# SCH_DART-Flight-Computer-4_2024-07-14.net
KiCad netlist of a schematic drawn in EasyEDA
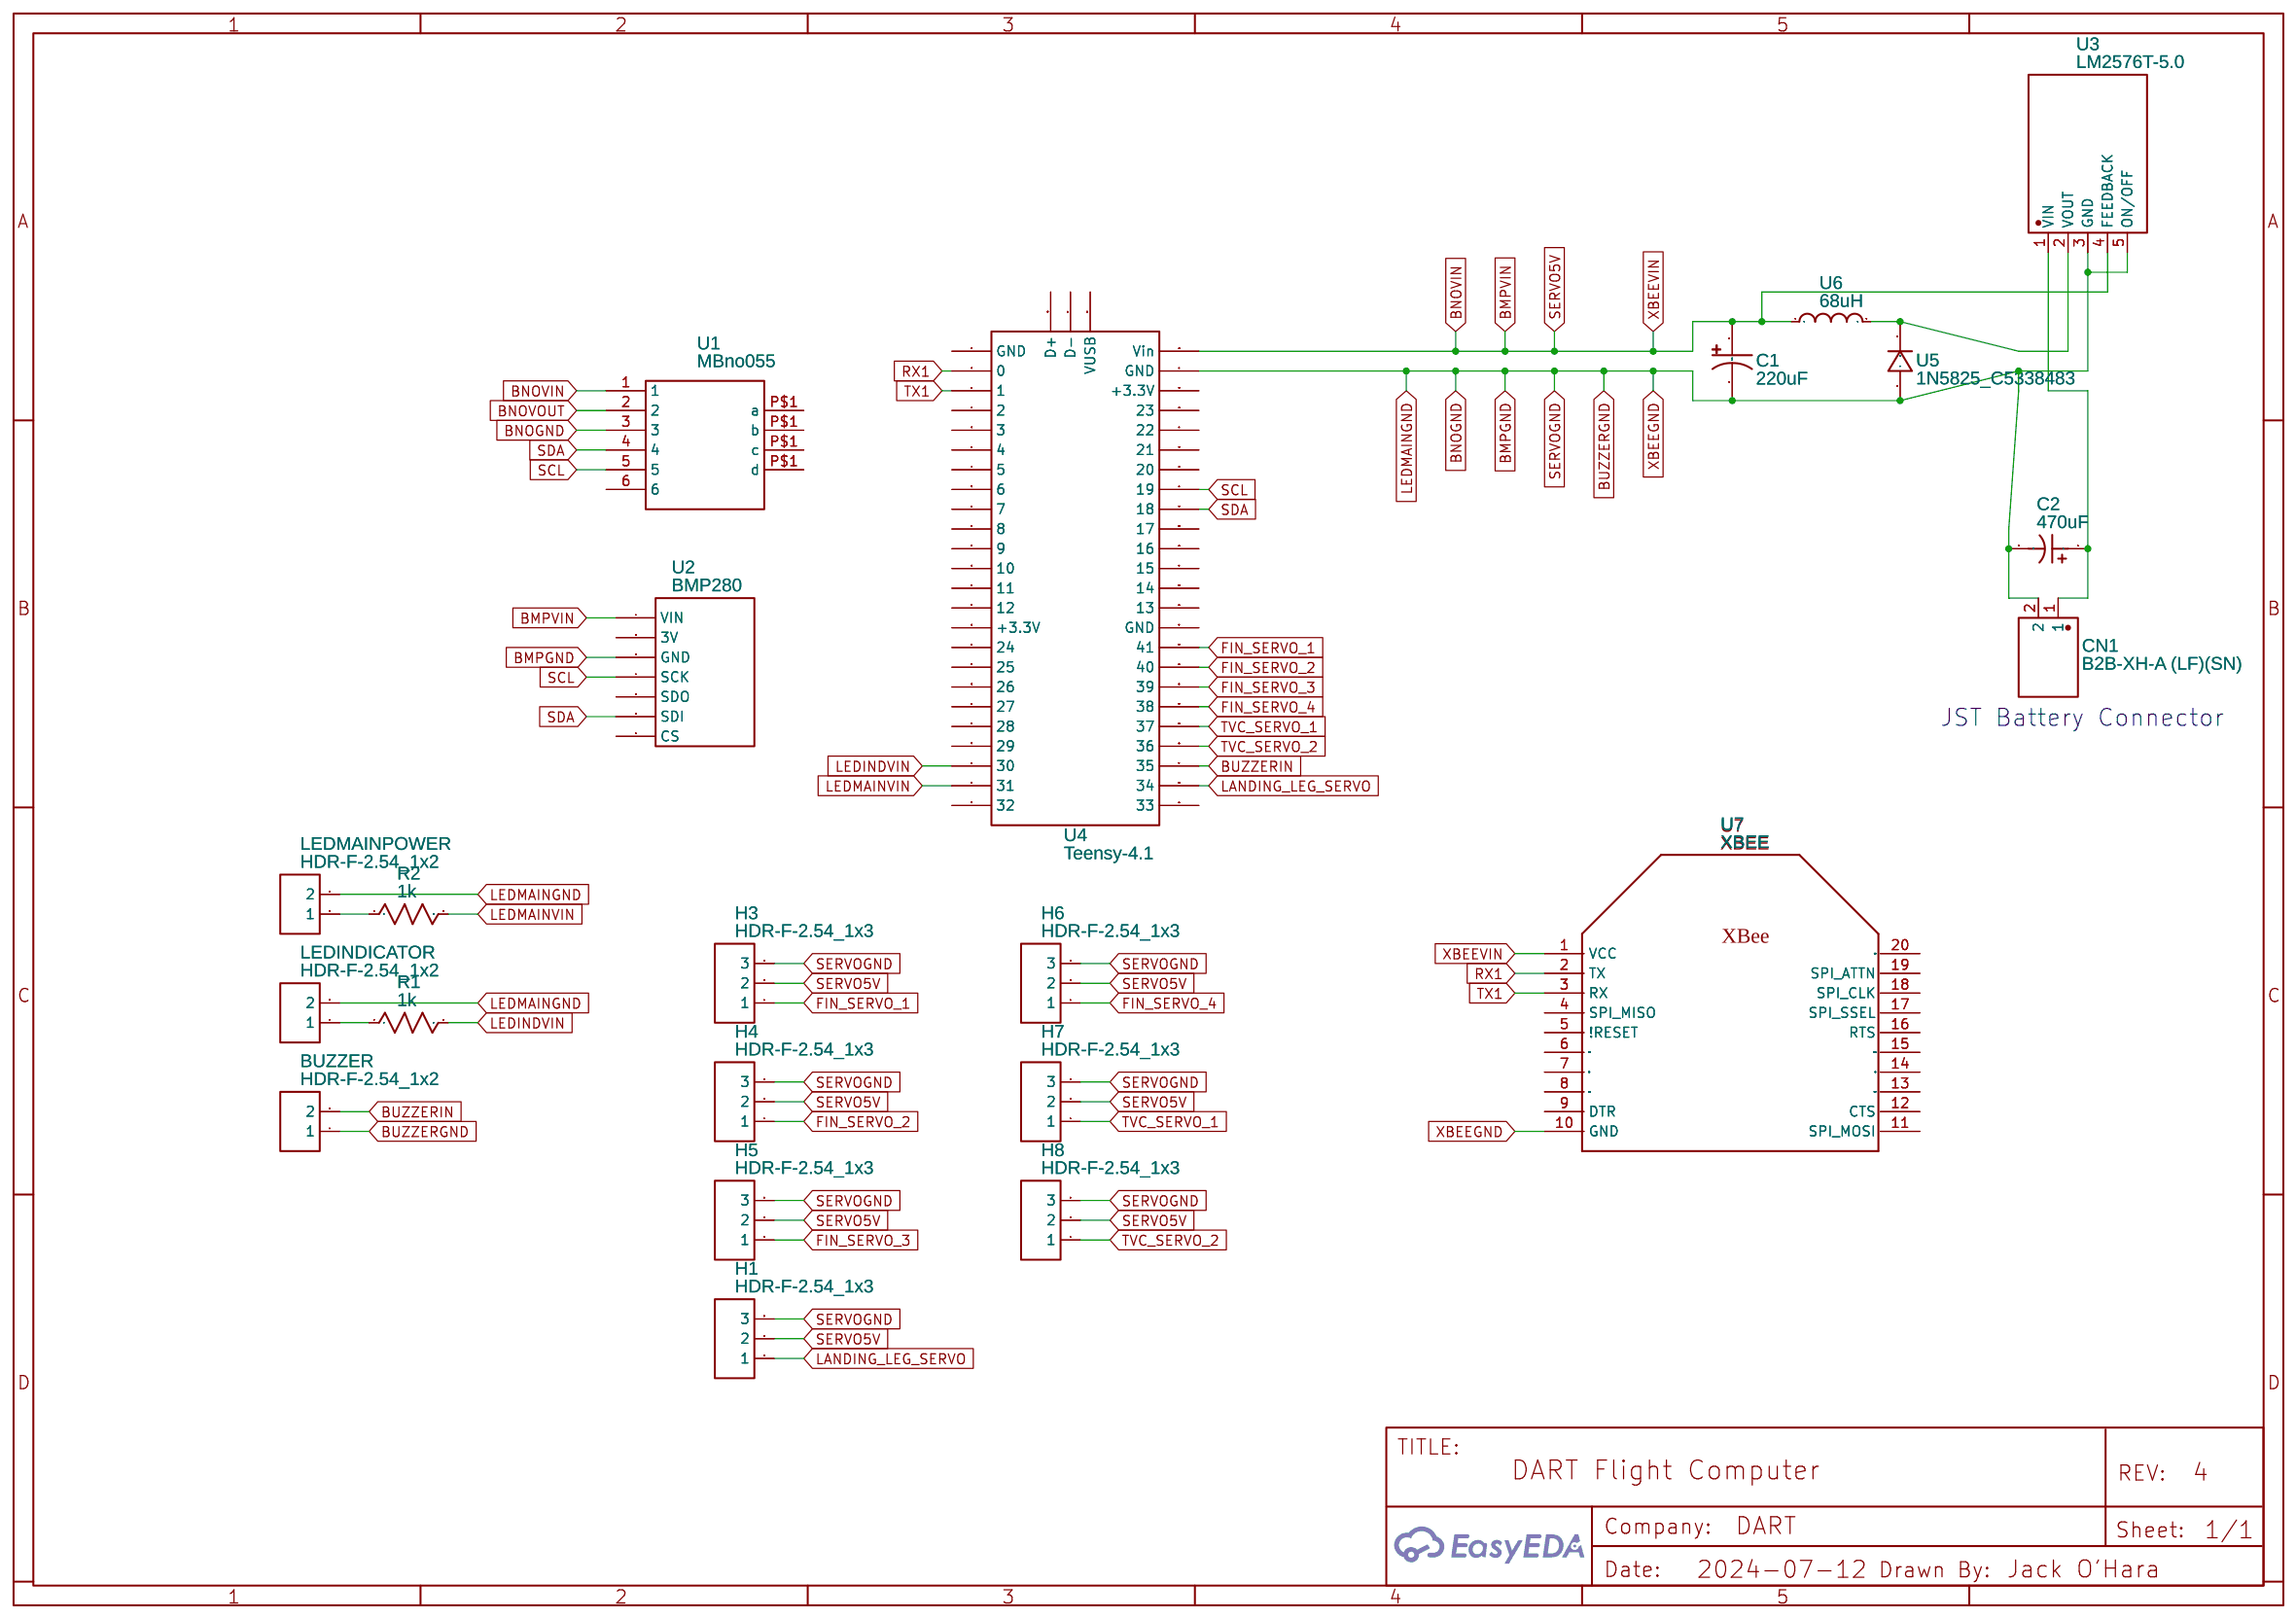
[diagram p0: schematic sheet]

(export (version "E")
  (design (tool "Eeschema 10.0.6"))
  (components
    (comp (ref "BUZZER") (value "HDR-F-2.54_1x2") (libsource (lib "") (part "HDR-F-2.54_1x2_1")))
    (comp (ref "C1")
      (value "220uF")
      (fields (field (name "Manufacturer Part") "UPW1E221MPD") (field (name "Manufacturer") "Nichicon(尼吉康)"))
      (libsource (lib "") (part "UPW1E221MPD"))
    )
    (comp (ref "C2")
      (value "470uF")
      (fields (field (name "Manufacturer Part") "152EC0399") (field (name "Manufacturer") "KNSCHA(科尼盛)"))
      (libsource (lib "") (part "152EC0399"))
    )
    (comp (ref "CN1")
      (value "B2B-XH-A (LF)(SN)")
      (fields (field (name "Manufacturer Part") "B2B-XH-A(LF)(SN)") (field (name "Manufacturer") "JST"))
      (libsource (lib "") (part "B2B-XH-A (LF)(SN)"))
    )
    (comp (ref "H1") (value "HDR-F-2.54_1x3") (libsource (lib "") (part "HDR-F-2.54_1x3")))
    (comp (ref "H3") (value "HDR-F-2.54_1x3") (libsource (lib "") (part "HDR-F-2.54_1x3")))
    (comp (ref "H4") (value "HDR-F-2.54_1x3") (libsource (lib "") (part "HDR-F-2.54_1x3")))
    (comp (ref "H5") (value "HDR-F-2.54_1x3") (libsource (lib "") (part "HDR-F-2.54_1x3")))
    (comp (ref "H6") (value "HDR-F-2.54_1x3") (libsource (lib "") (part "HDR-F-2.54_1x3")))
    (comp (ref "H7") (value "HDR-F-2.54_1x3") (libsource (lib "") (part "HDR-F-2.54_1x3")))
    (comp (ref "H8") (value "HDR-F-2.54_1x3") (libsource (lib "") (part "HDR-F-2.54_1x3")))
    (comp (ref "LEDINDICATOR") (value "HDR-F-2.54_1x2") (libsource (lib "") (part "HDR-F-2.54_1x2")))
    (comp (ref "LEDMAINPOWER") (value "HDR-F-2.54_1x2") (libsource (lib "") (part "HDR-F-2.54_1x2_2")))
    (comp (ref "R1") (value "1k") (libsource (lib "") (part "R_0603_US")))
    (comp (ref "R2") (value "1k") (libsource (lib "") (part "R_0603_US")))
    (comp (ref "U1") (value "MBno055") (libsource (lib "") (part "MBno055")))
    (comp (ref "U2") (value "BMP280") (libsource (lib "") (part "BMP280")))
    (comp (ref "U3")
      (value "LM2576T-5.0")
      (fields (field (name "Manufacturer") "HTC"))
      (libsource (lib "") (part "LM2576T-5.0"))
    )
    (comp (ref "U4") (value "Teensy-4.1") (libsource (lib "") (part "Teensy-4.1")))
    (comp (ref "U5")
      (value "1N5825_C5338483")
      (fields (field (name "Manufacturer Part") "1N5825") (field (name "Manufacturer") "SUNMATE(森美特)"))
      (libsource (lib "") (part "1N5825_C5338483"))
    )
    (comp (ref "U6")
      (value "68uH")
      (fields (field (name "Manufacturer Part") "SRR1210-680M") (field (name "Manufacturer") "BOURNS"))
      (libsource (lib "") (part "SRR1210-680M"))
    )
    (comp (ref "U7") (value "XBEE") (libsource (lib "") (part "XBEE")))
  )
  (nets
    (net (code "1") (name "BMPGND") (class "Default")
      (node (ref "BUZZER") (pin "1") (pinfunction "1_1") (pintype "input"))
      (node (ref "C1") (pin "2") (pinfunction "2_2") (pintype "unspecified"))
      (node (ref "C2") (pin "2") (pinfunction "2_2") (pintype "input"))
      (node (ref "CN1") (pin "2") (pinfunction "2_2") (pintype "unspecified"))
      (node (ref "H1") (pin "3") (pinfunction "3_3") (pintype "input"))
      (node (ref "H3") (pin "3") (pinfunction "3_3") (pintype "input"))
      (node (ref "H4") (pin "3") (pinfunction "3_3") (pintype "input"))
      (node (ref "H5") (pin "3") (pinfunction "3_3") (pintype "input"))
      (node (ref "H6") (pin "3") (pinfunction "3_3") (pintype "input"))
      (node (ref "H7") (pin "3") (pinfunction "3_3") (pintype "input"))
      (node (ref "H8") (pin "3") (pinfunction "3_3") (pintype "input"))
      (node (ref "LEDINDICATOR") (pin "2") (pinfunction "2_2") (pintype "input"))
      (node (ref "LEDMAINPOWER") (pin "2") (pinfunction "2_2") (pintype "input"))
      (node (ref "U1") (pin "3") (pinfunction "3_3") (pintype "unspecified"))
      (node (ref "U2") (pin "5") (pinfunction "GND_5") (pintype "unspecified"))
      (node (ref "U3") (pin "3") (pinfunction "GND_3") (pintype "unspecified"))
      (node (ref "U3") (pin "5") (pinfunction "ON/OFF_5") (pintype "unspecified"))
      (node (ref "U4") (pin "47") (pinfunction "GND_47") (pintype "unspecified"))
      (node (ref "U5") (pin "2") (pinfunction "A_2") (pintype "unspecified"))
      (node (ref "U7") (pin "10") (pinfunction "GND_10") (pintype "unspecified"))
    )
    (net (code "2") (name "BMPVIN") (class "Default")
      (node (ref "C1") (pin "1") (pinfunction "1_1") (pintype "unspecified"))
      (node (ref "H1") (pin "2") (pinfunction "2_2") (pintype "input"))
      (node (ref "H3") (pin "2") (pinfunction "2_2") (pintype "input"))
      (node (ref "H4") (pin "2") (pinfunction "2_2") (pintype "input"))
      (node (ref "H5") (pin "2") (pinfunction "2_2") (pintype "input"))
      (node (ref "H6") (pin "2") (pinfunction "2_2") (pintype "input"))
      (node (ref "H7") (pin "2") (pinfunction "2_2") (pintype "input"))
      (node (ref "H8") (pin "2") (pinfunction "2_2") (pintype "input"))
      (node (ref "U1") (pin "1") (pinfunction "1_1") (pintype "unspecified"))
      (node (ref "U2") (pin "7") (pinfunction "VIN_7") (pintype "unspecified"))
      (node (ref "U3") (pin "4") (pinfunction "FEEDBACK_4") (pintype "unspecified"))
      (node (ref "U4") (pin "48") (pinfunction "Vin_48") (pintype "unspecified"))
      (node (ref "U6") (pin "1") (pinfunction "1_1") (pintype "unspecified"))
      (node (ref "U7") (pin "1") (pinfunction "VCC_1") (pintype "unspecified"))
    )
    (net (code "3") (name "BNOVOUT") (class "Default")
      (node (ref "U1") (pin "2") (pinfunction "2_2") (pintype "unspecified"))
    )
    (net (code "4") (name "BUZZERIN") (class "Default")
      (node (ref "BUZZER") (pin "2") (pinfunction "2_2") (pintype "input"))
      (node (ref "U4") (pin "27") (pinfunction "35_27") (pintype "unspecified"))
    )
    (net (code "5") (name "FIN_SERVO_1") (class "Default")
      (node (ref "H3") (pin "1") (pinfunction "1_1") (pintype "input"))
      (node (ref "U4") (pin "33") (pinfunction "41_33") (pintype "unspecified"))
    )
    (net (code "6") (name "FIN_SERVO_2") (class "Default")
      (node (ref "H4") (pin "1") (pinfunction "1_1") (pintype "input"))
      (node (ref "U4") (pin "32") (pinfunction "40_32") (pintype "unspecified"))
    )
    (net (code "7") (name "FIN_SERVO_3") (class "Default")
      (node (ref "H5") (pin "1") (pinfunction "1_1") (pintype "input"))
      (node (ref "U4") (pin "31") (pinfunction "39_31") (pintype "unspecified"))
    )
    (net (code "8") (name "FIN_SERVO_4") (class "Default")
      (node (ref "H6") (pin "1") (pinfunction "1_1") (pintype "input"))
      (node (ref "U4") (pin "30") (pinfunction "38_30") (pintype "unspecified"))
    )
    (net (code "9") (name "LANDING_LEG_SERVO") (class "Default")
      (node (ref "H1") (pin "1") (pinfunction "1_1") (pintype "input"))
      (node (ref "U4") (pin "26") (pinfunction "34_26") (pintype "unspecified"))
    )
    (net (code "10") (name "LEDINDVIN") (class "Default")
      (node (ref "R1") (pin "2") (pinfunction "2_2") (pintype "unspecified"))
      (node (ref "U4") (pin "22") (pinfunction "30_22") (pintype "unspecified"))
    )
    (net (code "11") (name "LEDMAINVIN") (class "Default")
      (node (ref "R2") (pin "2") (pinfunction "2_2") (pintype "unspecified"))
      (node (ref "U4") (pin "23") (pinfunction "31_23") (pintype "unspecified"))
    )
    (net (code "12") (name "Net-(LEDINDICATOR-Pad1)") (class "Default")
      (node (ref "LEDINDICATOR") (pin "1") (pinfunction "1_1") (pintype "input"))
      (node (ref "R1") (pin "1") (pinfunction "1_1") (pintype "unspecified"))
    )
    (net (code "13") (name "Net-(LEDMAINPOWER-Pad1)") (class "Default")
      (node (ref "LEDMAINPOWER") (pin "1") (pinfunction "1_1") (pintype "input"))
      (node (ref "R2") (pin "1") (pinfunction "1_1") (pintype "unspecified"))
    )
    (net (code "14") (name "Net-(U3-VIN)") (class "Default")
      (node (ref "C2") (pin "1") (pinfunction "1_1") (pintype "input"))
      (node (ref "CN1") (pin "1") (pinfunction "1_1") (pintype "unspecified"))
      (node (ref "U3") (pin "1") (pinfunction "VIN_1") (pintype "unspecified"))
    )
    (net (code "15") (name "Net-(U3-VOUT)") (class "Default")
      (node (ref "U3") (pin "2") (pinfunction "VOUT_2") (pintype "unspecified"))
      (node (ref "U5") (pin "1") (pinfunction "C_1") (pintype "unspecified"))
      (node (ref "U6") (pin "2") (pinfunction "2_2") (pintype "unspecified"))
    )
    (net (code "16") (name "RX1") (class "Default")
      (node (ref "U4") (pin "2") (pinfunction "0_2") (pintype "unspecified"))
      (node (ref "U7") (pin "2") (pinfunction "TX_2") (pintype "output"))
    )
    (net (code "17") (name "SCL") (class "Default")
      (node (ref "U1") (pin "5") (pinfunction "5_5") (pintype "unspecified"))
      (node (ref "U2") (pin "4") (pinfunction "SCK_4") (pintype "unspecified"))
      (node (ref "U4") (pin "41") (pinfunction "19_41") (pintype "unspecified"))
    )
    (net (code "18") (name "SDA") (class "Default")
      (node (ref "U1") (pin "4") (pinfunction "4_4") (pintype "unspecified"))
      (node (ref "U2") (pin "2") (pinfunction "SDI_2") (pintype "unspecified"))
      (node (ref "U4") (pin "40") (pinfunction "18_40") (pintype "unspecified"))
    )
    (net (code "19") (name "TVC_SERVO_1") (class "Default")
      (node (ref "H7") (pin "1") (pinfunction "1_1") (pintype "input"))
      (node (ref "U4") (pin "29") (pinfunction "37_29") (pintype "unspecified"))
    )
    (net (code "20") (name "TVC_SERVO_2") (class "Default")
      (node (ref "H8") (pin "1") (pinfunction "1_1") (pintype "input"))
      (node (ref "U4") (pin "28") (pinfunction "36_28") (pintype "unspecified"))
    )
    (net (code "21") (name "TX1") (class "Default")
      (node (ref "U4") (pin "3") (pinfunction "1_3") (pintype "unspecified"))
      (node (ref "U7") (pin "3") (pinfunction "RX_3") (pintype "input"))
    )
    (net (code "22") (name "unconnected-(U1-Pad6)") (class "Default")
      (node (ref "U1") (pin "6") (pinfunction "6_6") (pintype "unspecified"))
    )
    (net (code "23") (name "unconnected-(U1-a-PadP$1)") (class "Default")
      (node (ref "U1") (pin "P$1") (pinfunction "a_P$1") (pintype "unspecified"))
    )
    (net (code "24") (name "unconnected-(U1-b-PadP$1)") (class "Default")
      (node (ref "U1") (pin "P$1") (pinfunction "b_P$1") (pintype "unspecified"))
    )
    (net (code "25") (name "unconnected-(U1-c-PadP$1)") (class "Default")
      (node (ref "U1") (pin "P$1") (pinfunction "c_P$1") (pintype "unspecified"))
    )
    (net (code "26") (name "unconnected-(U1-d-PadP$1)") (class "Default")
      (node (ref "U1") (pin "P$1") (pinfunction "d_P$1") (pintype "unspecified"))
    )
    (net (code "27") (name "unconnected-(U2-3V-Pad6)") (class "Default")
      (node (ref "U2") (pin "6") (pinfunction "3V_6") (pintype "unspecified"))
    )
    (net (code "28") (name "unconnected-(U2-CS-Pad1)") (class "Default")
      (node (ref "U2") (pin "1") (pinfunction "CS_1") (pintype "unspecified"))
    )
    (net (code "29") (name "unconnected-(U2-SDO-Pad3)") (class "Default")
      (node (ref "U2") (pin "3") (pinfunction "SDO_3") (pintype "unspecified"))
    )
    (net (code "30") (name "unconnected-(U4-+3.3V-Pad15)") (class "Default")
      (node (ref "U4") (pin "15") (pinfunction "+3.3V_15") (pintype "unspecified"))
    )
    (net (code "31") (name "unconnected-(U4-+3.3V-Pad46)") (class "Default")
      (node (ref "U4") (pin "46") (pinfunction "+3.3V_46") (pintype "unspecified"))
    )
    (net (code "32") (name "unconnected-(U4-2-Pad4)") (class "Default")
      (node (ref "U4") (pin "4") (pinfunction "2_4") (pintype "unspecified"))
    )
    (net (code "33") (name "unconnected-(U4-3-Pad5)") (class "Default")
      (node (ref "U4") (pin "5") (pinfunction "3_5") (pintype "unspecified"))
    )
    (net (code "34") (name "unconnected-(U4-4-Pad6)") (class "Default")
      (node (ref "U4") (pin "6") (pinfunction "4_6") (pintype "unspecified"))
    )
    (net (code "35") (name "unconnected-(U4-5-Pad7)") (class "Default")
      (node (ref "U4") (pin "7") (pinfunction "5_7") (pintype "unspecified"))
    )
    (net (code "36") (name "unconnected-(U4-6-Pad8)") (class "Default")
      (node (ref "U4") (pin "8") (pinfunction "6_8") (pintype "unspecified"))
    )
    (net (code "37") (name "unconnected-(U4-7-Pad9)") (class "Default")
      (node (ref "U4") (pin "9") (pinfunction "7_9") (pintype "unspecified"))
    )
    (net (code "38") (name "unconnected-(U4-8-Pad10)") (class "Default")
      (node (ref "U4") (pin "10") (pinfunction "8_10") (pintype "unspecified"))
    )
    (net (code "39") (name "unconnected-(U4-9-Pad11)") (class "Default")
      (node (ref "U4") (pin "11") (pinfunction "9_11") (pintype "unspecified"))
    )
    (net (code "40") (name "unconnected-(U4-10-Pad12)") (class "Default")
      (node (ref "U4") (pin "12") (pinfunction "10_12") (pintype "unspecified"))
    )
    (net (code "41") (name "unconnected-(U4-11-Pad13)") (class "Default")
      (node (ref "U4") (pin "13") (pinfunction "11_13") (pintype "unspecified"))
    )
    (net (code "42") (name "unconnected-(U4-12-Pad14)") (class "Default")
      (node (ref "U4") (pin "14") (pinfunction "12_14") (pintype "unspecified"))
    )
    (net (code "43") (name "unconnected-(U4-13-Pad35)") (class "Default")
      (node (ref "U4") (pin "35") (pinfunction "13_35") (pintype "unspecified"))
    )
    (net (code "44") (name "unconnected-(U4-14-Pad36)") (class "Default")
      (node (ref "U4") (pin "36") (pinfunction "14_36") (pintype "unspecified"))
    )
    (net (code "45") (name "unconnected-(U4-15-Pad37)") (class "Default")
      (node (ref "U4") (pin "37") (pinfunction "15_37") (pintype "unspecified"))
    )
    (net (code "46") (name "unconnected-(U4-16-Pad38)") (class "Default")
      (node (ref "U4") (pin "38") (pinfunction "16_38") (pintype "unspecified"))
    )
    (net (code "47") (name "unconnected-(U4-17-Pad39)") (class "Default")
      (node (ref "U4") (pin "39") (pinfunction "17_39") (pintype "unspecified"))
    )
    (net (code "48") (name "unconnected-(U4-20-Pad42)") (class "Default")
      (node (ref "U4") (pin "42") (pinfunction "20_42") (pintype "unspecified"))
    )
    (net (code "49") (name "unconnected-(U4-21-Pad43)") (class "Default")
      (node (ref "U4") (pin "43") (pinfunction "21_43") (pintype "unspecified"))
    )
    (net (code "50") (name "unconnected-(U4-22-Pad44)") (class "Default")
      (node (ref "U4") (pin "44") (pinfunction "22_44") (pintype "unspecified"))
    )
    (net (code "51") (name "unconnected-(U4-23-Pad45)") (class "Default")
      (node (ref "U4") (pin "45") (pinfunction "23_45") (pintype "unspecified"))
    )
    (net (code "52") (name "unconnected-(U4-24-Pad16)") (class "Default")
      (node (ref "U4") (pin "16") (pinfunction "24_16") (pintype "unspecified"))
    )
    (net (code "53") (name "unconnected-(U4-25-Pad17)") (class "Default")
      (node (ref "U4") (pin "17") (pinfunction "25_17") (pintype "unspecified"))
    )
    (net (code "54") (name "unconnected-(U4-26-Pad18)") (class "Default")
      (node (ref "U4") (pin "18") (pinfunction "26_18") (pintype "unspecified"))
    )
    (net (code "55") (name "unconnected-(U4-27-Pad19)") (class "Default")
      (node (ref "U4") (pin "19") (pinfunction "27_19") (pintype "unspecified"))
    )
    (net (code "56") (name "unconnected-(U4-28-Pad20)") (class "Default")
      (node (ref "U4") (pin "20") (pinfunction "28_20") (pintype "unspecified"))
    )
    (net (code "57") (name "unconnected-(U4-29-Pad21)") (class "Default")
      (node (ref "U4") (pin "21") (pinfunction "29_21") (pintype "unspecified"))
    )
    (net (code "58") (name "unconnected-(U4-32-Pad24)") (class "Default")
      (node (ref "U4") (pin "24") (pinfunction "32_24") (pintype "unspecified"))
    )
    (net (code "59") (name "unconnected-(U4-33-Pad25)") (class "Default")
      (node (ref "U4") (pin "25") (pinfunction "33_25") (pintype "unspecified"))
    )
    (net (code "60") (name "unconnected-(U4-D+-Pad66)") (class "Default")
      (node (ref "U4") (pin "66") (pinfunction "D+_66") (pintype "unspecified"))
    )
    (net (code "61") (name "unconnected-(U4-D--Pad67)") (class "Default")
      (node (ref "U4") (pin "67") (pinfunction "D-_67") (pintype "unspecified"))
    )
    (net (code "62") (name "unconnected-(U4-GND-Pad1)") (class "Default")
      (node (ref "U4") (pin "1") (pinfunction "GND_1") (pintype "unspecified"))
    )
    (net (code "63") (name "unconnected-(U4-GND-Pad34)") (class "Default")
      (node (ref "U4") (pin "34") (pinfunction "GND_34") (pintype "unspecified"))
    )
    (net (code "64") (name "unconnected-(U4-VUSB-Pad52)") (class "Default")
      (node (ref "U4") (pin "52") (pinfunction "VUSB_52") (pintype "unspecified"))
    )
    (net (code "65") (name "unconnected-(U7-!RESET-Pad5)") (class "Default")
      (node (ref "U7") (pin "5") (pinfunction "!RESET_5") (pintype "input"))
    )
    (net (code "66") (name "unconnected-(U7-AD0DIO0-Pad20)") (class "Default")
      (node (ref "U7") (pin "20") (pinfunction "AD0DIO0_20") (pintype "unspecified"))
    )
    (net (code "67") (name "unconnected-(U7-ASCAD5DIO5-Pad15)") (class "Default")
      (node (ref "U7") (pin "15") (pinfunction "ASCAD5DIO5_15") (pintype "unspecified"))
    )
    (net (code "68") (name "unconnected-(U7-CTS-Pad12)") (class "Default")
      (node (ref "U7") (pin "12") (pinfunction "CTS_12") (pintype "unspecified"))
    )
    (net (code "69") (name "unconnected-(U7-DTR-Pad9)") (class "Default")
      (node (ref "U7") (pin "9") (pinfunction "DTR_9") (pintype "unspecified"))
    )
    (net (code "70") (name "unconnected-(U7-ONSLEEP-Pad13)") (class "Default")
      (node (ref "U7") (pin "13") (pinfunction "ONSLEEP_13") (pintype "output"))
    )
    (net (code "71") (name "unconnected-(U7-PWM0RSSI-Pad6)") (class "Default")
      (node (ref "U7") (pin "6") (pinfunction "PWM0RSSI_6") (pintype "output"))
    )
    (net (code "72") (name "unconnected-(U7-PWM1-Pad7)") (class "Default")
      (node (ref "U7") (pin "7") (pinfunction "PWM1_7") (pintype "output"))
    )
    (net (code "73") (name "unconnected-(U7-RESERVED-Pad8)") (class "Default")
      (node (ref "U7") (pin "8") (pinfunction "RESERVED_8") (pintype "unspecified"))
    )
    (net (code "74") (name "unconnected-(U7-RTS-Pad16)") (class "Default")
      (node (ref "U7") (pin "16") (pinfunction "RTS_16") (pintype "unspecified"))
    )
    (net (code "75") (name "unconnected-(U7-SPI_ATTN-Pad19)") (class "Default")
      (node (ref "U7") (pin "19") (pinfunction "SPI_ATTN_19") (pintype "unspecified"))
    )
    (net (code "76") (name "unconnected-(U7-SPI_CLK-Pad18)") (class "Default")
      (node (ref "U7") (pin "18") (pinfunction "SPI_CLK_18") (pintype "unspecified"))
    )
    (net (code "77") (name "unconnected-(U7-SPI_MISO-Pad4)") (class "Default")
      (node (ref "U7") (pin "4") (pinfunction "SPI_MISO_4") (pintype "output"))
    )
    (net (code "78") (name "unconnected-(U7-SPI_MOSI-Pad11)") (class "Default")
      (node (ref "U7") (pin "11") (pinfunction "SPI_MOSI_11") (pintype "unspecified"))
    )
    (net (code "79") (name "unconnected-(U7-SPI_SSEL-Pad17)") (class "Default")
      (node (ref "U7") (pin "17") (pinfunction "SPI_SSEL_17") (pintype "unspecified"))
    )
    (net (code "80") (name "unconnected-(U7-VREF-Pad14)") (class "Default")
      (node (ref "U7") (pin "14") (pinfunction "VREF_14") (pintype "input"))
    )
  )
)
